# GrblPi_B_Industrial.net
KiCad netlist of a schematic drawn in EAGLE
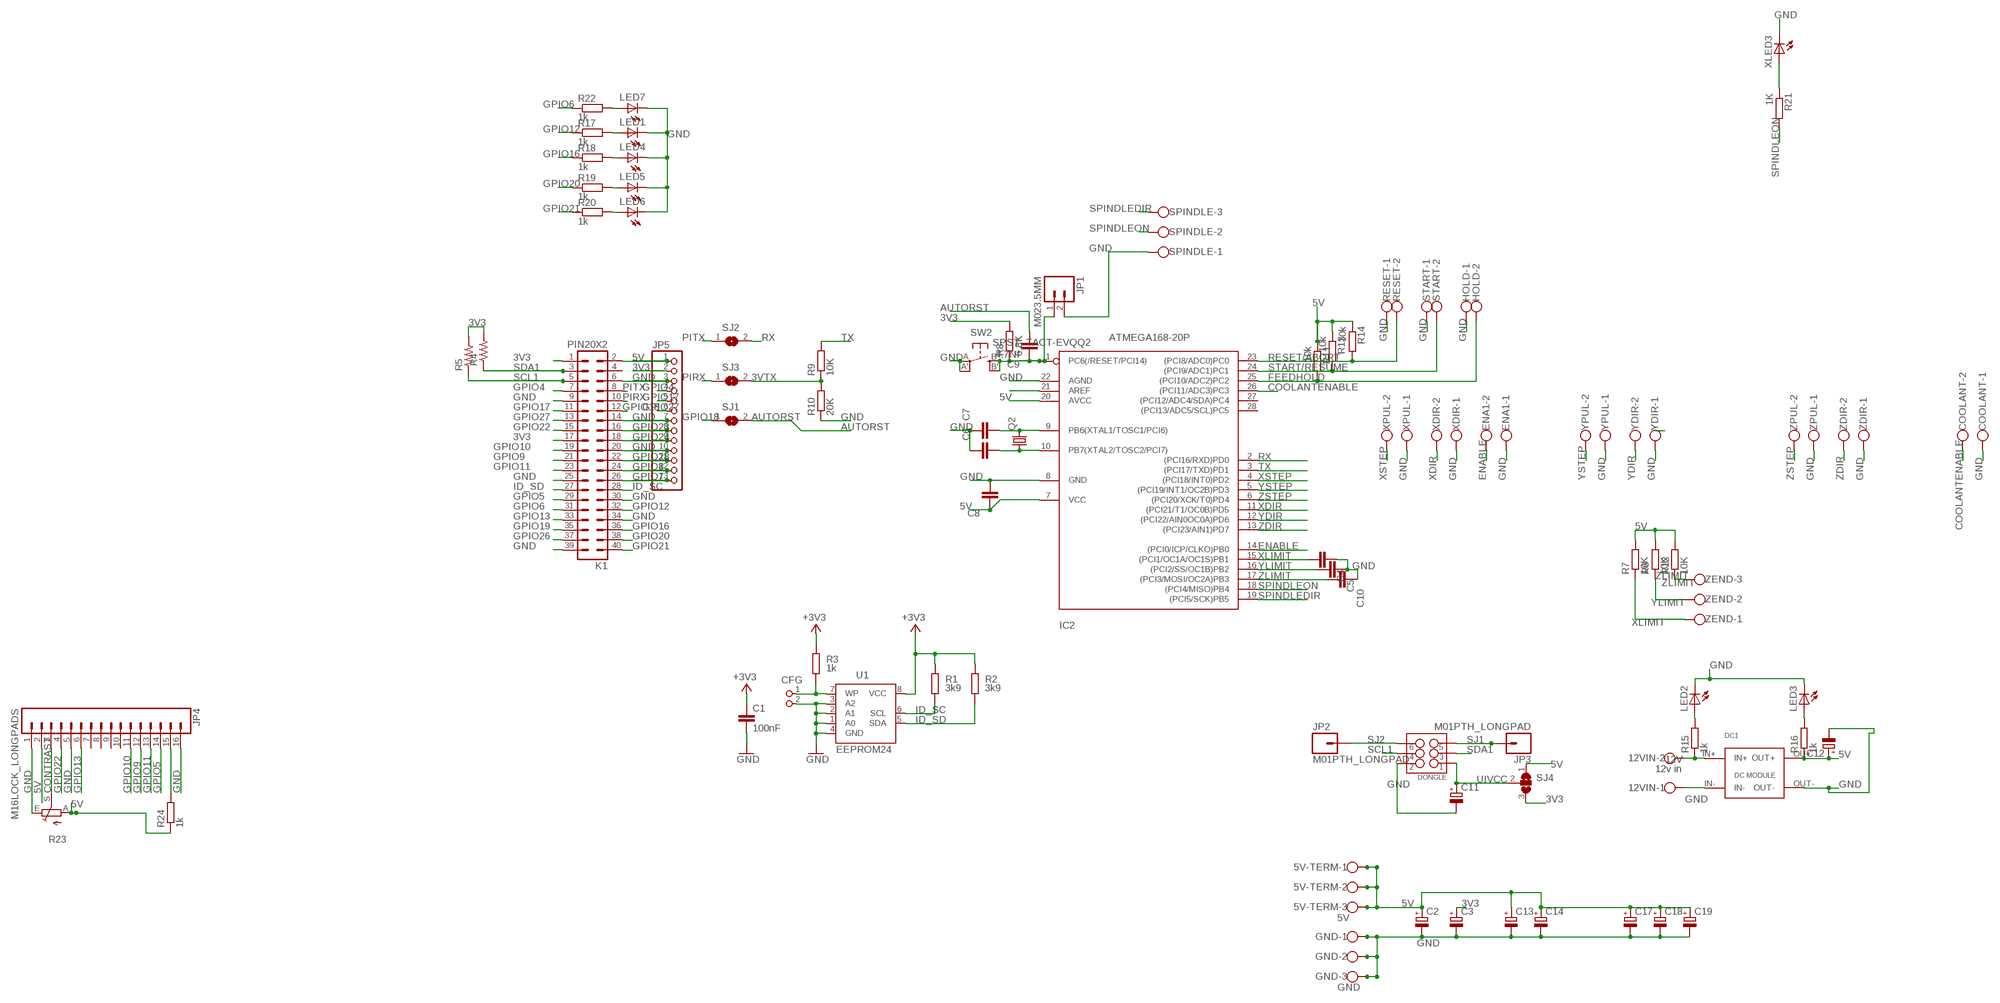
[diagram p0: schematic, sheet 1]

(export (version "E")
  (design (tool "Eeschema 10.0.6"))
  (components
    (comp (ref "5V-TERM")
      (value "5V")
      (footprint "eagle-import:W237-103")
      (fields (field (name "MPN") "237-103"))
      (libsource (lib "eagle-import") (part "W237-103"))
    )
    (comp (ref "12VIN")
      (value "12v in")
      (footprint "eagle-import:W237-102")
      (fields (field (name "MPN") "237-102"))
      (libsource (lib "eagle-import") (part "W237-102"))
    )
    (comp (ref "C1")
      (value "100nF")
      (footprint "eagle-import:C1206")
      (libsource (lib "eagle-import") (part "C-EUC1206"))
    )
    (comp (ref "C2")
      (value "CPOL-EU153CLV-0405")
      (footprint "eagle-import:153CLV-0405")
      (libsource (lib "eagle-import") (part "CPOL-EU153CLV-0405"))
    )
    (comp (ref "C3")
      (value "CPOL-EU153CLV-0405")
      (footprint "eagle-import:153CLV-0405")
      (libsource (lib "eagle-import") (part "CPOL-EU153CLV-0405"))
    )
    (comp (ref "C4")
      (value "CAPACITOR_NPOL-1206")
      (footprint "eagle-import:C1206")
      (libsource (lib "eagle-import") (part "CAPACITOR_NPOL-1206"))
    )
    (comp (ref "C5")
      (value "CAPACITOR_NPOL-1206")
      (footprint "eagle-import:C1206")
      (libsource (lib "eagle-import") (part "CAPACITOR_NPOL-1206"))
    )
    (comp (ref "C6")
      (value "CAPACITOR_NPOL-1206")
      (footprint "eagle-import:C1206")
      (libsource (lib "eagle-import") (part "CAPACITOR_NPOL-1206"))
    )
    (comp (ref "C7")
      (value "CAPACITOR_NPOL-1206")
      (footprint "eagle-import:C1206")
      (libsource (lib "eagle-import") (part "CAPACITOR_NPOL-1206"))
    )
    (comp (ref "C8")
      (value "CAPACITOR_NPOL-1206")
      (footprint "eagle-import:C1206")
      (libsource (lib "eagle-import") (part "CAPACITOR_NPOL-1206"))
    )
    (comp (ref "C9")
      (value "4.7Nf")
      (footprint "eagle-import:C1206")
      (libsource (lib "eagle-import") (part "CAPACITOR_NPOL-1206"))
    )
    (comp (ref "C10")
      (value "CAPACITOR_NPOL-1206")
      (footprint "eagle-import:C1206")
      (libsource (lib "eagle-import") (part "CAPACITOR_NPOL-1206"))
    )
    (comp (ref "C11")
      (value "CPOL-EU153CLV-0405")
      (footprint "eagle-import:153CLV-0405")
      (libsource (lib "eagle-import") (part "CPOL-EU153CLV-0405"))
    )
    (comp (ref "C12")
      (value "CPOL-EU153CLV-0405")
      (footprint "eagle-import:153CLV-0405")
      (libsource (lib "eagle-import") (part "CPOL-EU153CLV-0405"))
    )
    (comp (ref "C13")
      (value "CPOL-EU153CLV-0405")
      (footprint "eagle-import:153CLV-0405")
      (libsource (lib "eagle-import") (part "CPOL-EU153CLV-0405"))
    )
    (comp (ref "C14")
      (value "CPOL-EU153CLV-0405")
      (footprint "eagle-import:153CLV-0405")
      (libsource (lib "eagle-import") (part "CPOL-EU153CLV-0405"))
    )
    (comp (ref "C17")
      (value "CPOL-EU153CLV-0405")
      (footprint "eagle-import:153CLV-0405")
      (libsource (lib "eagle-import") (part "CPOL-EU153CLV-0405"))
    )
    (comp (ref "C18")
      (value "CPOL-EU153CLV-0405")
      (footprint "eagle-import:153CLV-0405")
      (libsource (lib "eagle-import") (part "CPOL-EU153CLV-0405"))
    )
    (comp (ref "C19")
      (value "CPOL-EU153CLV-0405")
      (footprint "eagle-import:153CLV-0405")
      (libsource (lib "eagle-import") (part "CPOL-EU153CLV-0405"))
    )
    (comp (ref "CFG")
      (value "PIN2_100")
      (footprint "eagle-import:PIN_W_2")
      (libsource (lib "eagle-import") (part "PIN2_100"))
    )
    (comp (ref "COOLANT")
      (value "W237-102")
      (footprint "eagle-import:W237-102")
      (fields (field (name "MPN") "237-102"))
      (libsource (lib "eagle-import") (part "W237-102"))
    )
    (comp (ref "DC1")
      (value "BUCKBOOST")
      (footprint "eagle-import:BUCKBOOST")
      (libsource (lib "eagle-import") (part "BUCKBOOST"))
    )
    (comp (ref "DONGLE")
      (value "M03X2SHROUD")
      (footprint "eagle-import:2X3-SHROUDED")
      (libsource (lib "eagle-import") (part "M03X2SHROUD"))
    )
    (comp (ref "ENA1")
      (value "W237-102")
      (footprint "eagle-import:W237-102")
      (fields (field (name "MPN") "237-102"))
      (libsource (lib "eagle-import") (part "W237-102"))
    )
    (comp (ref "GND")
      (value "GND")
      (footprint "eagle-import:W237-103")
      (fields (field (name "MPN") "237-103"))
      (libsource (lib "eagle-import") (part "W237-103"))
    )
    (comp (ref "HOLD")
      (value "W237-102")
      (footprint "eagle-import:W237-102")
      (fields (field (name "MPN") "237-102"))
      (libsource (lib "eagle-import") (part "W237-102"))
    )
    (comp (ref "IC2")
      (value "ATMEGA168-20P")
      (footprint "eagle-import:DIL28-3")
      (libsource (lib "eagle-import") (part "ATMEGA168P-20"))
    )
    (comp (ref "JP1")
      (value "M023.5MM")
      (footprint "eagle-import:SCREWTERMINAL-3.5MM-2")
      (libsource (lib "eagle-import") (part "M023.5MM"))
    )
    (comp (ref "JP2")
      (value "M01PTH_LONGPAD")
      (footprint "eagle-import:1X01_LONGPAD")
      (libsource (lib "eagle-import") (part "M01PTH_LONGPAD"))
    )
    (comp (ref "JP3")
      (value "M01PTH_LONGPAD")
      (footprint "eagle-import:1X01_LONGPAD")
      (libsource (lib "eagle-import") (part "M01PTH_LONGPAD"))
    )
    (comp (ref "JP4")
      (value "M16LOCK_LONGPADS")
      (footprint "eagle-import:1X16_LOCK_LONGPADS")
      (libsource (lib "eagle-import") (part "M16LOCK_LONGPADS"))
    )
    (comp (ref "JP5")
      (value "PINHD-1X13")
      (footprint "eagle-import:1X13")
      (libsource (lib "eagle-import") (part "PINHD-1X13"))
    )
    (comp (ref "K1")
      (value "PIN20X2")
      (footprint "eagle-import:PIN_20X2")
      (libsource (lib "eagle-import") (part "PIN20X2"))
    )
    (comp (ref "LED1")
      (value "LED5MM")
      (footprint "eagle-import:LED5MM")
      (libsource (lib "eagle-import") (part "LED5MM"))
    )
    (comp (ref "LED2")
      (value "LED5MM")
      (footprint "eagle-import:LED5MM")
      (libsource (lib "eagle-import") (part "LED5MM"))
    )
    (comp (ref "LED3")
      (value "LED5MM")
      (footprint "eagle-import:LED5MM")
      (libsource (lib "eagle-import") (part "LED5MM"))
    )
    (comp (ref "LED4")
      (value "LED5MM")
      (footprint "eagle-import:LED5MM")
      (libsource (lib "eagle-import") (part "LED5MM"))
    )
    (comp (ref "LED5")
      (value "LED5MM")
      (footprint "eagle-import:LED5MM")
      (libsource (lib "eagle-import") (part "LED5MM"))
    )
    (comp (ref "LED6")
      (value "LED5MM")
      (footprint "eagle-import:LED5MM")
      (libsource (lib "eagle-import") (part "LED5MM"))
    )
    (comp (ref "LED7")
      (value "LED5MM")
      (footprint "eagle-import:LED5MM")
      (libsource (lib "eagle-import") (part "LED5MM"))
    )
    (comp (ref "Q2")
      (value "CRYSTALHC49UP")
      (footprint "eagle-import:HC49UP")
      (libsource (lib "eagle-import") (part "CRYSTALHC49UP"))
    )
    (comp (ref "R1")
      (value "3k9")
      (footprint "eagle-import:M1206")
      (fields (field (name "TOLERANCE") "5%"))
      (libsource (lib "eagle-import") (part "R-EU_M1206"))
    )
    (comp (ref "R2")
      (value "3k9")
      (footprint "eagle-import:M1206")
      (fields (field (name "TOLERANCE") "5%"))
      (libsource (lib "eagle-import") (part "R-EU_M1206"))
    )
    (comp (ref "R3")
      (value "1k")
      (footprint "eagle-import:M1206")
      (fields (field (name "TOLERANCE") "5%"))
      (libsource (lib "eagle-import") (part "R-EU_M1206"))
    )
    (comp (ref "R4")
      (value "R-US_M1206")
      (footprint "eagle-import:M1206")
      (libsource (lib "eagle-import") (part "R-US_M1206"))
    )
    (comp (ref "R5")
      (value "R-US_M1206")
      (footprint "eagle-import:M1206")
      (libsource (lib "eagle-import") (part "R-US_M1206"))
    )
    (comp (ref "R6")
      (value "10K")
      (footprint "eagle-import:R1206")
      (libsource (lib "eagle-import") (part "RESISTOR-1206"))
    )
    (comp (ref "R7")
      (value "10K")
      (footprint "eagle-import:R1206")
      (libsource (lib "eagle-import") (part "RESISTOR-1206"))
    )
    (comp (ref "R8")
      (value "6.8K")
      (footprint "eagle-import:R1206")
      (libsource (lib "eagle-import") (part "RESISTOR-1206"))
    )
    (comp (ref "R9")
      (value "10K")
      (footprint "eagle-import:R1206")
      (libsource (lib "eagle-import") (part "RESISTOR-1206"))
    )
    (comp (ref "R10")
      (value "20K")
      (footprint "eagle-import:R1206")
      (libsource (lib "eagle-import") (part "RESISTOR-1206"))
    )
    (comp (ref "R11")
      (value "10k")
      (footprint "eagle-import:R1206")
      (libsource (lib "eagle-import") (part "RESISTOR-1206"))
    )
    (comp (ref "R12")
      (value "10K")
      (footprint "eagle-import:R1206")
      (libsource (lib "eagle-import") (part "RESISTOR-1206"))
    )
    (comp (ref "R13")
      (value "10k")
      (footprint "eagle-import:R1206")
      (libsource (lib "eagle-import") (part "RESISTOR-1206"))
    )
    (comp (ref "R14")
      (value "10k")
      (footprint "eagle-import:R1206")
      (libsource (lib "eagle-import") (part "RESISTOR-1206"))
    )
    (comp (ref "R15")
      (value "1k")
      (footprint "eagle-import:R1206")
      (libsource (lib "eagle-import") (part "RESISTOR-1206"))
    )
    (comp (ref "R16")
      (value "1k")
      (footprint "eagle-import:R1206")
      (libsource (lib "eagle-import") (part "RESISTOR-1206"))
    )
    (comp (ref "R17")
      (value "1k")
      (footprint "eagle-import:R1206")
      (libsource (lib "eagle-import") (part "RESISTOR-1206"))
    )
    (comp (ref "R18")
      (value "1k")
      (footprint "eagle-import:R1206")
      (libsource (lib "eagle-import") (part "RESISTOR-1206"))
    )
    (comp (ref "R19")
      (value "1k")
      (footprint "eagle-import:R1206")
      (libsource (lib "eagle-import") (part "RESISTOR-1206"))
    )
    (comp (ref "R20")
      (value "1k")
      (footprint "eagle-import:R1206")
      (libsource (lib "eagle-import") (part "RESISTOR-1206"))
    )
    (comp (ref "R21")
      (value "1K")
      (footprint "eagle-import:R1206")
      (libsource (lib "eagle-import") (part "RESISTOR-1206"))
    )
    (comp (ref "R22")
      (value "1k")
      (footprint "eagle-import:R1206")
      (libsource (lib "eagle-import") (part "RESISTOR-1206"))
    )
    (comp (ref "R23")
      (value "TRIM_EU-CA6V")
      (footprint "eagle-import:CA6V")
      (libsource (lib "eagle-import") (part "TRIM_EU-CA6V"))
    )
    (comp (ref "R24")
      (value "1k")
      (footprint "eagle-import:R1206")
      (libsource (lib "eagle-import") (part "RESISTOR-1206"))
    )
    (comp (ref "RESET")
      (value "W237-102")
      (footprint "eagle-import:W237-102")
      (fields (field (name "MPN") "237-102"))
      (libsource (lib "eagle-import") (part "W237-102"))
    )
    (comp (ref "SJ1") (value "SJ") (footprint "eagle-import:SJ") (libsource (lib "eagle-import") (part "SJ")))
    (comp (ref "SJ2") (value "SJ") (footprint "eagle-import:SJ") (libsource (lib "eagle-import") (part "SJ")))
    (comp (ref "SJ3") (value "SJ") (footprint "eagle-import:SJ") (libsource (lib "eagle-import") (part "SJ")))
    (comp (ref "SJ4")
      (value "SJ2W")
      (footprint "eagle-import:SJ_2")
      (libsource (lib "eagle-import") (part "SJ2W"))
    )
    (comp (ref "SPINDLE")
      (value "W237-103")
      (footprint "eagle-import:W237-103")
      (fields (field (name "MPN") "237-103"))
      (libsource (lib "eagle-import") (part "W237-103"))
    )
    (comp (ref "START")
      (value "W237-102")
      (footprint "eagle-import:W237-102")
      (fields (field (name "MPN") "237-102"))
      (libsource (lib "eagle-import") (part "W237-102"))
    )
    (comp (ref "SW2")
      (value "SPST_TACT-EVQQ2")
      (footprint "eagle-import:EVQ-Q2")
      (libsource (lib "eagle-import") (part "SPST_TACT-EVQQ2"))
    )
    (comp (ref "U1")
      (value "EEPROM24")
      (footprint "eagle-import:SOIC8")
      (libsource (lib "eagle-import") (part "EEPROM24"))
    )
    (comp (ref "XDIR")
      (value "W237-102")
      (footprint "eagle-import:W237-102")
      (fields (field (name "MPN") "237-102"))
      (libsource (lib "eagle-import") (part "W237-102"))
    )
    (comp (ref "XLED3")
      (value "LEDCHIPLED_1206")
      (footprint "eagle-import:CHIPLED_1206")
      (libsource (lib "eagle-import") (part "LEDCHIPLED_1206"))
    )
    (comp (ref "XPUL")
      (value "W237-102")
      (footprint "eagle-import:W237-102")
      (fields (field (name "MPN") "237-102"))
      (libsource (lib "eagle-import") (part "W237-102"))
    )
    (comp (ref "YDIR")
      (value "W237-102")
      (footprint "eagle-import:W237-102")
      (fields (field (name "MPN") "237-102"))
      (libsource (lib "eagle-import") (part "W237-102"))
    )
    (comp (ref "YPUL")
      (value "W237-102")
      (footprint "eagle-import:W237-102")
      (fields (field (name "MPN") "237-102"))
      (libsource (lib "eagle-import") (part "W237-102"))
    )
    (comp (ref "ZDIR")
      (value "W237-102")
      (footprint "eagle-import:W237-102")
      (fields (field (name "MPN") "237-102"))
      (libsource (lib "eagle-import") (part "W237-102"))
    )
    (comp (ref "ZEND")
      (value "W237-103")
      (footprint "eagle-import:W237-103")
      (fields (field (name "MPN") "237-103"))
      (libsource (lib "eagle-import") (part "W237-103"))
    )
    (comp (ref "ZPUL")
      (value "W237-102")
      (footprint "eagle-import:W237-102")
      (fields (field (name "MPN") "237-102"))
      (libsource (lib "eagle-import") (part "W237-102"))
    )
  )
  (nets
    (net (code "1") (name "+3V3") (class "Default")
      (node (ref "C1") (pin "1") (pinfunction "1_1") (pintype "passive"))
      (node (ref "R1") (pin "2") (pinfunction "2_2") (pintype "passive"))
      (node (ref "R2") (pin "2") (pinfunction "2_2") (pintype "passive"))
      (node (ref "R3") (pin "2") (pinfunction "2_2") (pintype "passive"))
      (node (ref "U1") (pin "8") (pinfunction "VCC_8") (pintype "power_in"))
    )
    (net (code "2") (name "/3V3") (class "Default")
      (node (ref "C3") (pin "+") (pinfunction "+_+") (pintype "passive"))
      (node (ref "JP5") (pin "2") (pinfunction "2_2") (pintype "passive"))
      (node (ref "K1") (pin "1") (pinfunction "1_1") (pintype "passive"))
      (node (ref "K1") (pin "17") (pinfunction "17_17") (pintype "passive"))
      (node (ref "R4") (pin "2") (pinfunction "2_2") (pintype "passive"))
      (node (ref "R5") (pin "2") (pinfunction "2_2") (pintype "passive"))
      (node (ref "R8") (pin "2") (pinfunction "2_2") (pintype "passive"))
      (node (ref "SJ4") (pin "3") (pinfunction "3_3") (pintype "passive"))
    )
    (net (code "3") (name "/3VTX") (class "Default")
      (node (ref "R10") (pin "2") (pinfunction "2_2") (pintype "passive"))
      (node (ref "R9") (pin "1") (pinfunction "1_1") (pintype "passive"))
      (node (ref "SJ3") (pin "2") (pinfunction "2_2") (pintype "passive"))
    )
    (net (code "4") (name "/5V") (class "Default")
      (node (ref "5V-TERM") (pin "1") (pinfunction "KL_1") (pintype "passive"))
      (node (ref "5V-TERM") (pin "2") (pinfunction "KL_2") (pintype "passive"))
      (node (ref "5V-TERM") (pin "3") (pinfunction "KL_3") (pintype "passive"))
      (node (ref "C12") (pin "+") (pinfunction "+_+") (pintype "passive"))
      (node (ref "C13") (pin "+") (pinfunction "+_+") (pintype "passive"))
      (node (ref "C14") (pin "+") (pinfunction "+_+") (pintype "passive"))
      (node (ref "C17") (pin "+") (pinfunction "+_+") (pintype "passive"))
      (node (ref "C18") (pin "+") (pinfunction "+_+") (pintype "passive"))
      (node (ref "C19") (pin "+") (pinfunction "+_+") (pintype "passive"))
      (node (ref "C2") (pin "+") (pinfunction "+_+") (pintype "passive"))
      (node (ref "C8") (pin "1") (pinfunction "1_1") (pintype "passive"))
      (node (ref "DC1") (pin "OU+") (pinfunction "OUT+_OU+") (pintype "power_in"))
      (node (ref "IC2") (pin "20") (pinfunction "AVCC_20") (pintype "bidirectional"))
      (node (ref "IC2") (pin "7") (pinfunction "VCC_7") (pintype "bidirectional"))
      (node (ref "JP4") (pin "2") (pinfunction "2_2") (pintype "passive"))
      (node (ref "JP5") (pin "1") (pinfunction "1_1") (pintype "passive"))
      (node (ref "K1") (pin "2") (pinfunction "2_2") (pintype "passive"))
      (node (ref "R11") (pin "1") (pinfunction "1_1") (pintype "passive"))
      (node (ref "R12") (pin "2") (pinfunction "2_2") (pintype "passive"))
      (node (ref "R13") (pin "1") (pinfunction "1_1") (pintype "passive"))
      (node (ref "R14") (pin "1") (pinfunction "1_1") (pintype "passive"))
      (node (ref "R16") (pin "1") (pinfunction "1_1") (pintype "passive"))
      (node (ref "R23") (pin "A") (pinfunction "A_A") (pintype "passive"))
      (node (ref "R24") (pin "1") (pinfunction "1_1") (pintype "passive"))
      (node (ref "R6") (pin "2") (pinfunction "2_2") (pintype "passive"))
      (node (ref "R7") (pin "2") (pinfunction "2_2") (pintype "passive"))
      (node (ref "SJ4") (pin "1") (pinfunction "1_1") (pintype "passive"))
    )
    (net (code "5") (name "/12V") (class "Default")
      (node (ref "12VIN") (pin "2") (pinfunction "KL_2") (pintype "passive"))
      (node (ref "DC1") (pin "IN+") (pinfunction "IN+_IN+") (pintype "power_in"))
      (node (ref "R15") (pin "1") (pinfunction "1_1") (pintype "passive"))
    )
    (net (code "6") (name "/AUTORST") (class "Default")
      (node (ref "C9") (pin "2") (pinfunction "2_2") (pintype "passive"))
      (node (ref "SJ1") (pin "2") (pinfunction "2_2") (pintype "passive"))
    )
    (net (code "7") (name "/CONTRAST") (class "Default")
      (node (ref "JP4") (pin "3") (pinfunction "3_3") (pintype "passive"))
      (node (ref "R23") (pin "S") (pinfunction "S_S") (pintype "passive"))
    )
    (net (code "8") (name "/COOLANTENABLE") (class "Default")
      (node (ref "COOLANT") (pin "2") (pinfunction "KL_2") (pintype "passive"))
      (node (ref "IC2") (pin "26") (pinfunction "(PCI11/ADC3)PC3_26") (pintype "bidirectional"))
    )
    (net (code "9") (name "/ENABLE") (class "Default")
      (node (ref "ENA1") (pin "2") (pinfunction "KL_2") (pintype "passive"))
      (node (ref "IC2") (pin "14") (pinfunction "(PCI0/ICP/CLKO)PB0_14") (pintype "bidirectional"))
    )
    (net (code "10") (name "/FEEDHOLD") (class "Default")
      (node (ref "HOLD") (pin "2") (pinfunction "KL_2") (pintype "passive"))
      (node (ref "IC2") (pin "25") (pinfunction "(PCI10/ADC2)PC2_25") (pintype "bidirectional"))
      (node (ref "R11") (pin "2") (pinfunction "2_2") (pintype "passive"))
    )
    (net (code "11") (name "/GPIO4") (class "Default")
      (node (ref "JP5") (pin "4") (pinfunction "4_4") (pintype "passive"))
      (node (ref "K1") (pin "7") (pinfunction "7_7") (pintype "passive"))
    )
    (net (code "12") (name "/GPIO5") (class "Default")
      (node (ref "JP4") (pin "14") (pinfunction "14_14") (pintype "passive"))
      (node (ref "K1") (pin "29") (pinfunction "29_29") (pintype "passive"))
    )
    (net (code "13") (name "/GPIO6") (class "Default")
      (node (ref "K1") (pin "31") (pinfunction "31_31") (pintype "passive"))
      (node (ref "R22") (pin "1") (pinfunction "1_1") (pintype "passive"))
    )
    (net (code "14") (name "/GPIO7") (class "Default")
      (node (ref "JP5") (pin "13") (pinfunction "13_13") (pintype "passive"))
      (node (ref "K1") (pin "26") (pinfunction "26_26") (pintype "passive"))
    )
    (net (code "15") (name "/GPIO8") (class "Default")
      (node (ref "JP5") (pin "12") (pinfunction "12_12") (pintype "passive"))
      (node (ref "K1") (pin "24") (pinfunction "24_24") (pintype "passive"))
    )
    (net (code "16") (name "/GPIO9") (class "Default")
      (node (ref "JP4") (pin "12") (pinfunction "12_12") (pintype "passive"))
      (node (ref "K1") (pin "21") (pinfunction "21_21") (pintype "passive"))
    )
    (net (code "17") (name "/GPIO10") (class "Default")
      (node (ref "JP4") (pin "11") (pinfunction "11_11") (pintype "passive"))
      (node (ref "K1") (pin "19") (pinfunction "19_19") (pintype "passive"))
    )
    (net (code "18") (name "/GPIO11") (class "Default")
      (node (ref "JP4") (pin "13") (pinfunction "13_13") (pintype "passive"))
      (node (ref "K1") (pin "23") (pinfunction "23_23") (pintype "passive"))
    )
    (net (code "19") (name "/GPIO12") (class "Default")
      (node (ref "K1") (pin "32") (pinfunction "32_32") (pintype "passive"))
      (node (ref "R17") (pin "1") (pinfunction "1_1") (pintype "passive"))
    )
    (net (code "20") (name "/GPIO13") (class "Default")
      (node (ref "JP4") (pin "6") (pinfunction "6_6") (pintype "passive"))
      (node (ref "K1") (pin "33") (pinfunction "33_33") (pintype "passive"))
    )
    (net (code "21") (name "/GPIO16") (class "Default")
      (node (ref "K1") (pin "36") (pinfunction "36_36") (pintype "passive"))
      (node (ref "R18") (pin "1") (pinfunction "1_1") (pintype "passive"))
    )
    (net (code "22") (name "/GPIO17") (class "Default")
      (node (ref "JP5") (pin "5") (pinfunction "5_5") (pintype "passive"))
      (node (ref "K1") (pin "11") (pinfunction "11_11") (pintype "passive"))
    )
    (net (code "23") (name "/GPIO18") (class "Default")
      (node (ref "K1") (pin "12") (pinfunction "12_12") (pintype "passive"))
      (node (ref "SJ1") (pin "1") (pinfunction "1_1") (pintype "passive"))
    )
    (net (code "24") (name "/GPIO19") (class "Default")
      (node (ref "K1") (pin "35") (pinfunction "35_35") (pintype "passive"))
    )
    (net (code "25") (name "/GPIO20") (class "Default")
      (node (ref "K1") (pin "38") (pinfunction "38_38") (pintype "passive"))
      (node (ref "R19") (pin "1") (pinfunction "1_1") (pintype "passive"))
    )
    (net (code "26") (name "/GPIO21") (class "Default")
      (node (ref "K1") (pin "40") (pinfunction "40_40") (pintype "passive"))
      (node (ref "R20") (pin "1") (pinfunction "1_1") (pintype "passive"))
    )
    (net (code "27") (name "/GPIO22") (class "Default")
      (node (ref "JP4") (pin "4") (pinfunction "4_4") (pintype "passive"))
      (node (ref "K1") (pin "15") (pinfunction "15_15") (pintype "passive"))
    )
    (net (code "28") (name "/GPIO23") (class "Default")
      (node (ref "JP5") (pin "8") (pinfunction "8_8") (pintype "passive"))
      (node (ref "K1") (pin "16") (pinfunction "16_16") (pintype "passive"))
    )
    (net (code "29") (name "/GPIO24") (class "Default")
      (node (ref "JP5") (pin "9") (pinfunction "9_9") (pintype "passive"))
      (node (ref "K1") (pin "18") (pinfunction "18_18") (pintype "passive"))
    )
    (net (code "30") (name "/GPIO26") (class "Default")
      (node (ref "K1") (pin "37") (pinfunction "37_37") (pintype "passive"))
    )
    (net (code "31") (name "/GPIO27") (class "Default")
      (node (ref "JP5") (pin "6") (pinfunction "6_6") (pintype "passive"))
      (node (ref "K1") (pin "13") (pinfunction "13_13") (pintype "passive"))
    )
    (net (code "32") (name "/GPIO28") (class "Default")
      (node (ref "JP5") (pin "11") (pinfunction "11_11") (pintype "passive"))
      (node (ref "K1") (pin "22") (pinfunction "22_22") (pintype "passive"))
    )
    (net (code "33") (name "/ID_SC") (class "Default")
      (node (ref "K1") (pin "28") (pinfunction "28_28") (pintype "passive"))
      (node (ref "R1") (pin "1") (pinfunction "1_1") (pintype "passive"))
      (node (ref "U1") (pin "6") (pinfunction "SCL_6") (pintype "input"))
    )
    (net (code "34") (name "/ID_SD") (class "Default")
      (node (ref "K1") (pin "27") (pinfunction "27_27") (pintype "passive"))
      (node (ref "R2") (pin "1") (pinfunction "1_1") (pintype "passive"))
      (node (ref "U1") (pin "5") (pinfunction "SDA_5") (pintype "bidirectional"))
    )
    (net (code "35") (name "/PIRX") (class "Default")
      (node (ref "K1") (pin "10") (pinfunction "10_10") (pintype "passive"))
      (node (ref "SJ3") (pin "1") (pinfunction "1_1") (pintype "passive"))
    )
    (net (code "36") (name "/PITX") (class "Default")
      (node (ref "K1") (pin "8") (pinfunction "8_8") (pintype "passive"))
      (node (ref "SJ2") (pin "1") (pinfunction "1_1") (pintype "passive"))
    )
    (net (code "37") (name "/RESET{slash}ABORT") (class "Default")
      (node (ref "IC2") (pin "23") (pinfunction "(PCI8/ADC0)PC0_23") (pintype "bidirectional"))
      (node (ref "R14") (pin "2") (pinfunction "2_2") (pintype "passive"))
      (node (ref "RESET") (pin "2") (pinfunction "KL_2") (pintype "passive"))
    )
    (net (code "38") (name "/RX") (class "Default")
      (node (ref "IC2") (pin "2") (pinfunction "(PCI16/RXD)PD0_2") (pintype "bidirectional"))
      (node (ref "SJ2") (pin "2") (pinfunction "2_2") (pintype "passive"))
    )
    (net (code "39") (name "/SCL1") (class "Default")
      (node (ref "DONGLE") (pin "4") (pinfunction "4_4") (pintype "bidirectional"))
      (node (ref "K1") (pin "5") (pinfunction "5_5") (pintype "passive"))
      (node (ref "R5") (pin "1") (pinfunction "1_1") (pintype "passive"))
    )
    (net (code "40") (name "/SDA1") (class "Default")
      (node (ref "DONGLE") (pin "3") (pinfunction "3_3") (pintype "bidirectional"))
      (node (ref "K1") (pin "3") (pinfunction "3_3") (pintype "passive"))
      (node (ref "R4") (pin "1") (pinfunction "1_1") (pintype "passive"))
    )
    (net (code "41") (name "/SJ1") (class "Default")
      (node (ref "DONGLE") (pin "5") (pinfunction "5_5") (pintype "bidirectional"))
      (node (ref "JP3") (pin "1") (pinfunction "1_1") (pintype "passive"))
    )
    (net (code "42") (name "/SJ2") (class "Default")
      (node (ref "DONGLE") (pin "6") (pinfunction "6_6") (pintype "bidirectional"))
      (node (ref "JP2") (pin "1") (pinfunction "1_1") (pintype "passive"))
    )
    (net (code "43") (name "/SPINDLEDIR") (class "Default")
      (node (ref "IC2") (pin "19") (pinfunction "(PCI5/SCK)PB5_19") (pintype "bidirectional"))
      (node (ref "SPINDLE") (pin "3") (pinfunction "KL_3") (pintype "passive"))
    )
    (net (code "44") (name "/SPINDLEON") (class "Default")
      (node (ref "IC2") (pin "18") (pinfunction "(PCI4/MISO)PB4_18") (pintype "bidirectional"))
      (node (ref "R21") (pin "2") (pinfunction "2_2") (pintype "passive"))
      (node (ref "SPINDLE") (pin "2") (pinfunction "KL_2") (pintype "passive"))
    )
    (net (code "45") (name "/START{slash}RESUME") (class "Default")
      (node (ref "IC2") (pin "24") (pinfunction "(PCI9/ADC1)PC1_24") (pintype "bidirectional"))
      (node (ref "R13") (pin "2") (pinfunction "2_2") (pintype "passive"))
      (node (ref "START") (pin "2") (pinfunction "KL_2") (pintype "passive"))
    )
    (net (code "46") (name "/TX") (class "Default")
      (node (ref "IC2") (pin "3") (pinfunction "(PCI17/TXD)PD1_3") (pintype "bidirectional"))
      (node (ref "R9") (pin "2") (pinfunction "2_2") (pintype "passive"))
    )
    (net (code "47") (name "/UIVCC") (class "Default")
      (node (ref "C11") (pin "+") (pinfunction "+_+") (pintype "passive"))
      (node (ref "DONGLE") (pin "1") (pinfunction "1_1") (pintype "bidirectional"))
      (node (ref "SJ4") (pin "2") (pinfunction "2_2") (pintype "passive"))
    )
    (net (code "48") (name "/XDIR") (class "Default")
      (node (ref "IC2") (pin "11") (pinfunction "(PCI21/T1/OC0B)PD5_11") (pintype "bidirectional"))
      (node (ref "XDIR") (pin "2") (pinfunction "KL_2") (pintype "passive"))
    )
    (net (code "49") (name "/XLIMIT") (class "Default")
      (node (ref "C4") (pin "2") (pinfunction "2_2") (pintype "passive"))
      (node (ref "IC2") (pin "15") (pinfunction "(PCI1/OC1A/OC1S)PB1_15") (pintype "bidirectional"))
      (node (ref "R7") (pin "1") (pinfunction "1_1") (pintype "passive"))
      (node (ref "ZEND") (pin "1") (pinfunction "KL_1") (pintype "passive"))
    )
    (net (code "50") (name "/XSTEP") (class "Default")
      (node (ref "IC2") (pin "4") (pinfunction "(PCI18/INT0)PD2_4") (pintype "bidirectional"))
      (node (ref "XPUL") (pin "2") (pinfunction "KL_2") (pintype "passive"))
    )
    (net (code "51") (name "/YDIR") (class "Default")
      (node (ref "IC2") (pin "12") (pinfunction "(PCI22/AIN0OC0A)PD6_12") (pintype "bidirectional"))
      (node (ref "YDIR") (pin "2") (pinfunction "KL_2") (pintype "passive"))
    )
    (net (code "52") (name "/YLIMIT") (class "Default")
      (node (ref "C5") (pin "2") (pinfunction "2_2") (pintype "passive"))
      (node (ref "IC2") (pin "16") (pinfunction "(PCI2/SS/OC1B)PB2_16") (pintype "bidirectional"))
      (node (ref "R6") (pin "1") (pinfunction "1_1") (pintype "passive"))
      (node (ref "ZEND") (pin "2") (pinfunction "KL_2") (pintype "passive"))
    )
    (net (code "53") (name "/YSTEP") (class "Default")
      (node (ref "IC2") (pin "5") (pinfunction "(PCI19/INT1/OC2B)PD3_5") (pintype "bidirectional"))
      (node (ref "YPUL") (pin "2") (pinfunction "KL_2") (pintype "passive"))
    )
    (net (code "54") (name "/ZDIR") (class "Default")
      (node (ref "IC2") (pin "13") (pinfunction "(PCI23/AIN1)PD7_13") (pintype "bidirectional"))
      (node (ref "ZDIR") (pin "2") (pinfunction "KL_2") (pintype "passive"))
    )
    (net (code "55") (name "/ZLIMIT") (class "Default")
      (node (ref "C10") (pin "2") (pinfunction "2_2") (pintype "passive"))
      (node (ref "IC2") (pin "17") (pinfunction "(PCI3/MOSI/OC2A)PB3_17") (pintype "bidirectional"))
      (node (ref "R12") (pin "1") (pinfunction "1_1") (pintype "passive"))
      (node (ref "ZEND") (pin "3") (pinfunction "KL_3") (pintype "passive"))
    )
    (net (code "56") (name "/ZSTEP") (class "Default")
      (node (ref "IC2") (pin "6") (pinfunction "(PCI20/XCK/T0)PD4_6") (pintype "bidirectional"))
      (node (ref "ZPUL") (pin "2") (pinfunction "KL_2") (pintype "passive"))
    )
    (net (code "57") (name "GND") (class "Default")
      (node (ref "12VIN") (pin "1") (pinfunction "KL_1") (pintype "passive"))
      (node (ref "C1") (pin "2") (pinfunction "2_2") (pintype "passive"))
      (node (ref "C10") (pin "1") (pinfunction "1_1") (pintype "passive"))
      (node (ref "C11") (pin "-") (pinfunction "-_-") (pintype "passive"))
      (node (ref "C12") (pin "-") (pinfunction "-_-") (pintype "passive"))
      (node (ref "C13") (pin "-") (pinfunction "-_-") (pintype "passive"))
      (node (ref "C14") (pin "-") (pinfunction "-_-") (pintype "passive"))
      (node (ref "C17") (pin "-") (pinfunction "-_-") (pintype "passive"))
      (node (ref "C18") (pin "-") (pinfunction "-_-") (pintype "passive"))
      (node (ref "C19") (pin "-") (pinfunction "-_-") (pintype "passive"))
      (node (ref "C2") (pin "-") (pinfunction "-_-") (pintype "passive"))
      (node (ref "C3") (pin "-") (pinfunction "-_-") (pintype "passive"))
      (node (ref "C4") (pin "1") (pinfunction "1_1") (pintype "passive"))
      (node (ref "C5") (pin "1") (pinfunction "1_1") (pintype "passive"))
      (node (ref "C6") (pin "1") (pinfunction "1_1") (pintype "passive"))
      (node (ref "C7") (pin "1") (pinfunction "1_1") (pintype "passive"))
      (node (ref "C8") (pin "2") (pinfunction "2_2") (pintype "passive"))
      (node (ref "CFG") (pin "2") (pinfunction "2_2") (pintype "passive"))
      (node (ref "COOLANT") (pin "1") (pinfunction "KL_1") (pintype "passive"))
      (node (ref "DC1") (pin "IN-") (pinfunction "IN-_IN-") (pintype "bidirectional"))
      (node (ref "DC1") (pin "OUT-") (pinfunction "OUT-_OUT-") (pintype "bidirectional"))
      (node (ref "DONGLE") (pin "2") (pinfunction "2_2") (pintype "bidirectional"))
      (node (ref "ENA1") (pin "1") (pinfunction "KL_1") (pintype "passive"))
      (node (ref "GND") (pin "1") (pinfunction "KL_1") (pintype "passive"))
      (node (ref "GND") (pin "2") (pinfunction "KL_2") (pintype "passive"))
      (node (ref "GND") (pin "3") (pinfunction "KL_3") (pintype "passive"))
      (node (ref "HOLD") (pin "1") (pinfunction "KL_1") (pintype "passive"))
      (node (ref "IC2") (pin "22") (pinfunction "AGND_22") (pintype "bidirectional"))
      (node (ref "IC2") (pin "8") (pinfunction "GND_8") (pintype "bidirectional"))
      (node (ref "JP1") (pin "2") (pinfunction "2_2") (pintype "passive"))
      (node (ref "JP4") (pin "1") (pinfunction "1_1") (pintype "passive"))
      (node (ref "JP4") (pin "16") (pinfunction "16_16") (pintype "passive"))
      (node (ref "JP4") (pin "5") (pinfunction "5_5") (pintype "passive"))
      (node (ref "JP5") (pin "10") (pinfunction "10_10") (pintype "passive"))
      (node (ref "JP5") (pin "3") (pinfunction "3_3") (pintype "passive"))
      (node (ref "JP5") (pin "7") (pinfunction "7_7") (pintype "passive"))
      (node (ref "K1") (pin "14") (pinfunction "14_14") (pintype "passive"))
      (node (ref "K1") (pin "20") (pinfunction "20_20") (pintype "passive"))
      (node (ref "K1") (pin "25") (pinfunction "25_25") (pintype "passive"))
      (node (ref "K1") (pin "30") (pinfunction "30_30") (pintype "passive"))
      (node (ref "K1") (pin "34") (pinfunction "34_34") (pintype "passive"))
      (node (ref "K1") (pin "39") (pinfunction "39_39") (pintype "passive"))
      (node (ref "K1") (pin "6") (pinfunction "6_6") (pintype "passive"))
      (node (ref "K1") (pin "9") (pinfunction "9_9") (pintype "passive"))
      (node (ref "LED1") (pin "K") (pinfunction "C_K") (pintype "passive"))
      (node (ref "LED2") (pin "K") (pinfunction "C_K") (pintype "passive"))
      (node (ref "LED3") (pin "K") (pinfunction "C_K") (pintype "passive"))
      (node (ref "LED4") (pin "K") (pinfunction "C_K") (pintype "passive"))
      (node (ref "LED5") (pin "K") (pinfunction "C_K") (pintype "passive"))
      (node (ref "LED6") (pin "K") (pinfunction "C_K") (pintype "passive"))
      (node (ref "LED7") (pin "K") (pinfunction "C_K") (pintype "passive"))
      (node (ref "R10") (pin "1") (pinfunction "1_1") (pintype "passive"))
      (node (ref "R23") (pin "E") (pinfunction "E_E") (pintype "passive"))
      (node (ref "RESET") (pin "1") (pinfunction "KL_1") (pintype "passive"))
      (node (ref "SPINDLE") (pin "1") (pinfunction "KL_1") (pintype "passive"))
      (node (ref "START") (pin "1") (pinfunction "KL_1") (pintype "passive"))
      (node (ref "SW2") (pin "A") (pinfunction "P_A") (pintype "passive"))
      (node (ref "SW2") (pin "A'") (pinfunction "P1_A'") (pintype "passive"))
      (node (ref "U1") (pin "1") (pinfunction "A0_1") (pintype "input"))
      (node (ref "U1") (pin "2") (pinfunction "A1_2") (pintype "input"))
      (node (ref "U1") (pin "3") (pinfunction "A2_3") (pintype "input"))
      (node (ref "U1") (pin "4") (pinfunction "GND_4") (pintype "power_in"))
      (node (ref "XDIR") (pin "1") (pinfunction "KL_1") (pintype "passive"))
      (node (ref "XLED3") (pin "C") (pinfunction "C_C") (pintype "passive"))
      (node (ref "XPUL") (pin "1") (pinfunction "KL_1") (pintype "passive"))
      (node (ref "YDIR") (pin "1") (pinfunction "KL_1") (pintype "passive"))
      (node (ref "YPUL") (pin "1") (pinfunction "KL_1") (pintype "passive"))
      (node (ref "ZDIR") (pin "1") (pinfunction "KL_1") (pintype "passive"))
      (node (ref "ZPUL") (pin "1") (pinfunction "KL_1") (pintype "passive"))
    )
    (net (code "58") (name "Net-(IC2-PB6(XTAL1{slash}TOSC1{slash}PCI6))") (class "Default")
      (node (ref "C7") (pin "2") (pinfunction "2_2") (pintype "passive"))
      (node (ref "IC2") (pin "9") (pinfunction "PB6(XTAL1/TOSC1/PCI6)_9") (pintype "bidirectional"))
      (node (ref "Q2") (pin "2") (pinfunction "2_2") (pintype "passive"))
    )
    (net (code "59") (name "Net-(IC2-PB7(XTAL2{slash}TOSC2{slash}PCI7))") (class "Default")
      (node (ref "C6") (pin "2") (pinfunction "2_2") (pintype "passive"))
      (node (ref "IC2") (pin "10") (pinfunction "PB7(XTAL2/TOSC2/PCI7)_10") (pintype "bidirectional"))
      (node (ref "Q2") (pin "1") (pinfunction "1_1") (pintype "passive"))
    )
    (net (code "60") (name "Net-(IC2-PC6({slash}RESET{slash}PCI14))") (class "Default")
      (node (ref "C9") (pin "1") (pinfunction "1_1") (pintype "passive"))
      (node (ref "IC2") (pin "1") (pinfunction "PC6(/RESET/PCI14)_1") (pintype "bidirectional"))
      (node (ref "JP1") (pin "1") (pinfunction "1_1") (pintype "passive"))
      (node (ref "R8") (pin "1") (pinfunction "1_1") (pintype "passive"))
      (node (ref "SW2") (pin "B") (pinfunction "S_B") (pintype "passive"))
      (node (ref "SW2") (pin "B'") (pinfunction "S1_B'") (pintype "passive"))
    )
    (net (code "61") (name "Net-(JP4-Pad15)") (class "Default")
      (node (ref "JP4") (pin "15") (pinfunction "15_15") (pintype "passive"))
      (node (ref "R24") (pin "2") (pinfunction "2_2") (pintype "passive"))
    )
    (net (code "62") (name "Net-(LED1-PadA)") (class "Default")
      (node (ref "LED1") (pin "A") (pinfunction "A_A") (pintype "passive"))
      (node (ref "R17") (pin "2") (pinfunction "2_2") (pintype "passive"))
    )
    (net (code "63") (name "Net-(LED2-PadA)") (class "Default")
      (node (ref "LED2") (pin "A") (pinfunction "A_A") (pintype "passive"))
      (node (ref "R15") (pin "2") (pinfunction "2_2") (pintype "passive"))
    )
    (net (code "64") (name "Net-(LED3-PadA)") (class "Default")
      (node (ref "LED3") (pin "A") (pinfunction "A_A") (pintype "passive"))
      (node (ref "R16") (pin "2") (pinfunction "2_2") (pintype "passive"))
    )
    (net (code "65") (name "Net-(LED4-PadA)") (class "Default")
      (node (ref "LED4") (pin "A") (pinfunction "A_A") (pintype "passive"))
      (node (ref "R18") (pin "2") (pinfunction "2_2") (pintype "passive"))
    )
    (net (code "66") (name "Net-(LED5-PadA)") (class "Default")
      (node (ref "LED5") (pin "A") (pinfunction "A_A") (pintype "passive"))
      (node (ref "R19") (pin "2") (pinfunction "2_2") (pintype "passive"))
    )
    (net (code "67") (name "Net-(LED6-PadA)") (class "Default")
      (node (ref "LED6") (pin "A") (pinfunction "A_A") (pintype "passive"))
      (node (ref "R20") (pin "2") (pinfunction "2_2") (pintype "passive"))
    )
    (net (code "68") (name "Net-(LED7-PadA)") (class "Default")
      (node (ref "LED7") (pin "A") (pinfunction "A_A") (pintype "passive"))
      (node (ref "R22") (pin "2") (pinfunction "2_2") (pintype "passive"))
    )
    (net (code "69") (name "Net-(R21-Pad1)") (class "Default")
      (node (ref "R21") (pin "1") (pinfunction "1_1") (pintype "passive"))
      (node (ref "XLED3") (pin "A") (pinfunction "A_A") (pintype "passive"))
    )
    (net (code "70") (name "Net-(U1-WP)") (class "Default")
      (node (ref "CFG") (pin "1") (pinfunction "1_1") (pintype "passive"))
      (node (ref "R3") (pin "1") (pinfunction "1_1") (pintype "passive"))
      (node (ref "U1") (pin "7") (pinfunction "WP_7") (pintype "input"))
    )
    (net (code "71") (name "unconnected-(IC2-(PCI12{slash}ADC4{slash}SDA)PC4-Pad27)") (class "Default")
      (node (ref "IC2") (pin "27") (pinfunction "(PCI12/ADC4/SDA)PC4_27") (pintype "bidirectional"))
    )
    (net (code "72") (name "unconnected-(IC2-(PCI13{slash}ADC5{slash}SCL)PC5-Pad28)") (class "Default")
      (node (ref "IC2") (pin "28") (pinfunction "(PCI13/ADC5/SCL)PC5_28") (pintype "bidirectional"))
    )
    (net (code "73") (name "unconnected-(IC2-AREF-Pad21)") (class "Default")
      (node (ref "IC2") (pin "21") (pinfunction "AREF_21") (pintype "bidirectional"))
    )
    (net (code "74") (name "unconnected-(JP4-Pad7)") (class "Default")
      (node (ref "JP4") (pin "7") (pinfunction "7_7") (pintype "passive"))
    )
    (net (code "75") (name "unconnected-(JP4-Pad8)") (class "Default")
      (node (ref "JP4") (pin "8") (pinfunction "8_8") (pintype "passive"))
    )
    (net (code "76") (name "unconnected-(JP4-Pad9)") (class "Default")
      (node (ref "JP4") (pin "9") (pinfunction "9_9") (pintype "passive"))
    )
    (net (code "77") (name "unconnected-(JP4-Pad10)") (class "Default")
      (node (ref "JP4") (pin "10") (pinfunction "10_10") (pintype "passive"))
    )
    (net (code "78") (name "unconnected-(K1-Pad4)") (class "Default")
      (node (ref "K1") (pin "4") (pinfunction "4_4") (pintype "passive"))
    )
  )
)
